# EasyEDA.net
KiCad netlist of a schematic drawn in EasyEDA Pro
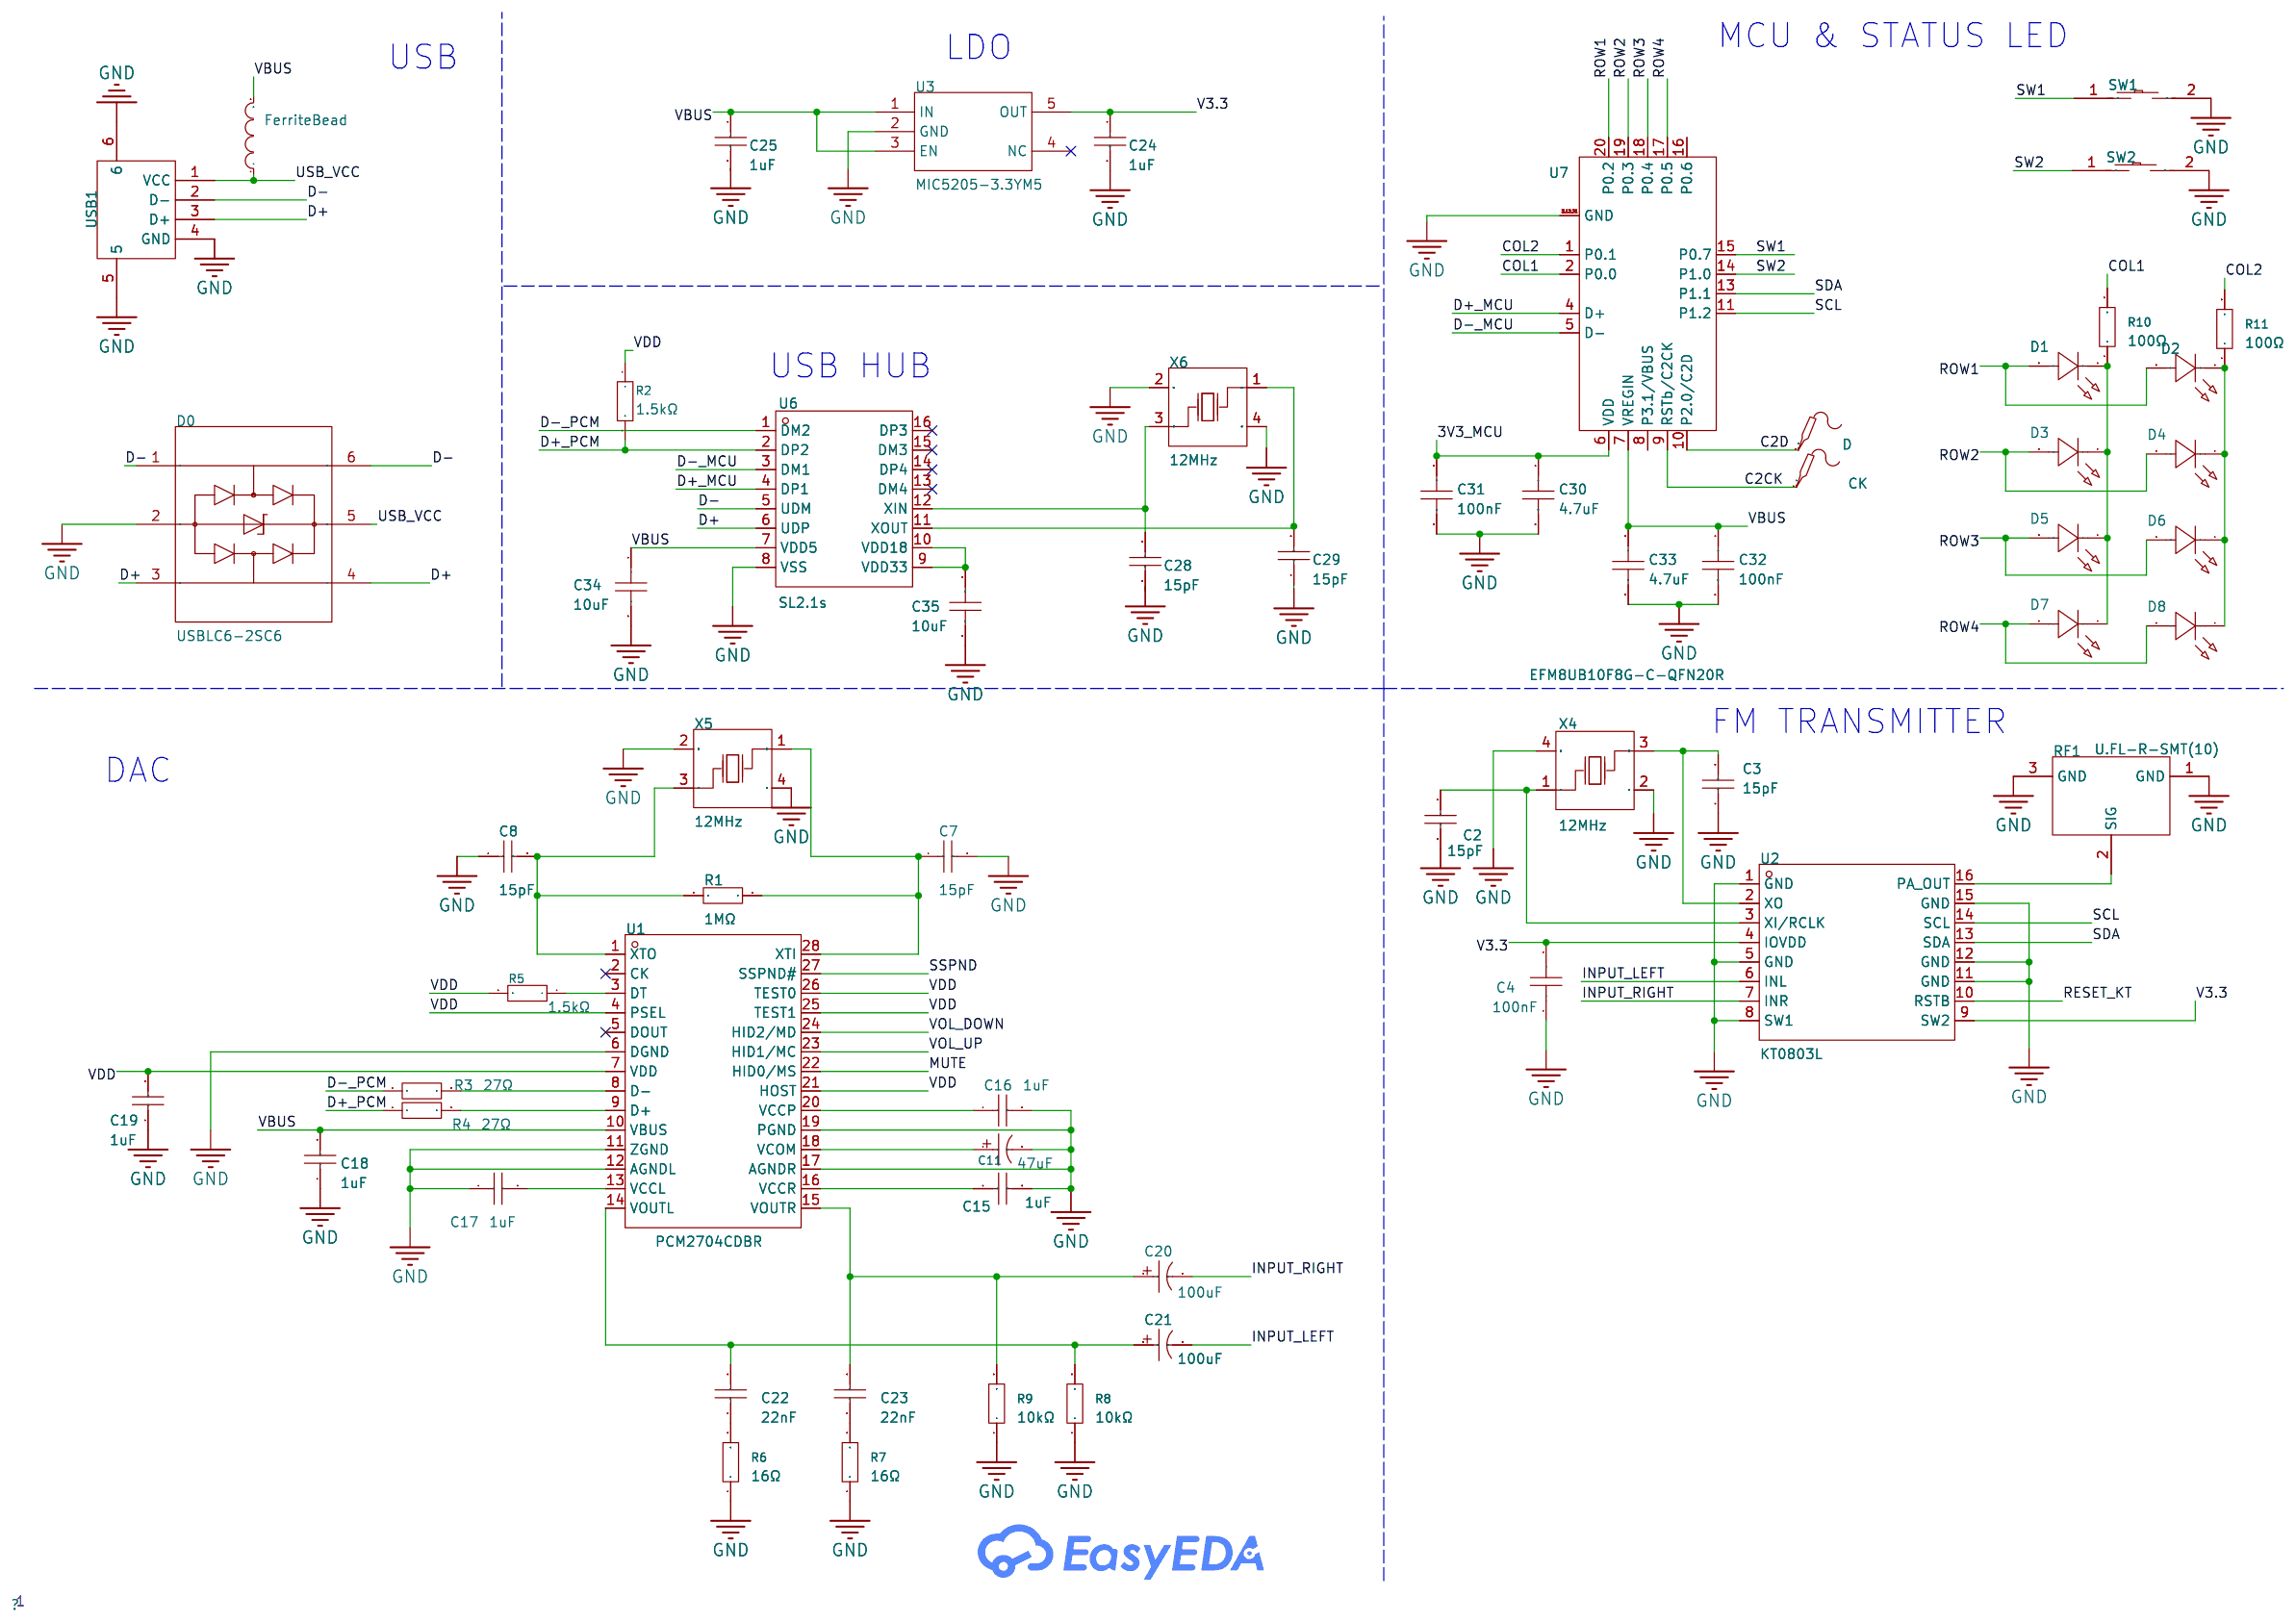
[diagram p0: schematic sheet]

(export (version "E")
  (design (tool "Eeschema 10.0.6"))
  (components
    (comp (ref "C2")
      (value "15pF")
      (footprint "easyedapro:C0402")
      (fields (field (name "Manufacturer Part") "0402CG150J500NT") (field (name "Manufacturer") "FH(风华)"))
      (libsource (lib "easyedapro") (part "0402CG150J500NT"))
    )
    (comp (ref "C3")
      (value "15pF")
      (footprint "easyedapro:C0402")
      (fields (field (name "Manufacturer Part") "0402CG150J500NT") (field (name "Manufacturer") "FH(风华)"))
      (libsource (lib "easyedapro") (part "0402CG150J500NT"))
    )
    (comp (ref "C4")
      (value "100nF")
      (footprint "easyedapro:C0402")
      (fields
        (field (name "Manufacturer Part") "CL05B104KO5NNNC")
        (field (name "Manufacturer") "SAMSUNG(三星)")
      )
      (libsource (lib "easyedapro") (part "CL05B104KO5NNNC"))
    )
    (comp (ref "C7")
      (value "15pF")
      (footprint "easyedapro:C0402")
      (fields (field (name "Manufacturer Part") "0402CG150J500NT") (field (name "Manufacturer") "FH(风华)"))
      (libsource (lib "easyedapro") (part "0402CG150J500NT"))
    )
    (comp (ref "C8")
      (value "15pF")
      (footprint "easyedapro:C0402")
      (fields
        (field (name "Manufacturer Part") "GJM1555C1H150FB01D")
        (field (name "Manufacturer") "muRata(村田)")
      )
      (libsource (lib "easyedapro") (part "0402CG150J500NT"))
    )
    (comp (ref "C11")
      (value "47uF")
      (footprint "easyedapro:CAP-SMD_BD5.0-L5.3-W5.3-FD")
      (fields (field (name "Manufacturer Part") "RVT1C470M0505") (field (name "Manufacturer") "HONOR(荣誉)"))
      (libsource (lib "easyedapro") (part "RVT1C470M0505"))
    )
    (comp (ref "C15")
      (value "1uF")
      (footprint "easyedapro:C0603")
      (fields
        (field (name "Manufacturer Part") "CL05A105KP5NNNC")
        (field (name "Manufacturer") "SAMSUNG(三星)")
      )
      (libsource (lib "easyedapro") (part "CL10A105KO8NNNC"))
    )
    (comp (ref "C16")
      (value "1uF")
      (footprint "easyedapro:C0603")
      (fields
        (field (name "Manufacturer Part") "CL05A105KP5NNNC")
        (field (name "Manufacturer") "SAMSUNG(三星)")
      )
      (libsource (lib "easyedapro") (part "CL10A105KO8NNNC"))
    )
    (comp (ref "C17")
      (value "1uF")
      (footprint "easyedapro:C0603")
      (fields
        (field (name "Manufacturer Part") "CL05A105KP5NNNC")
        (field (name "Manufacturer") "SAMSUNG(三星)")
      )
      (libsource (lib "easyedapro") (part "CL10A105KO8NNNC"))
    )
    (comp (ref "C18")
      (value "1uF")
      (footprint "easyedapro:C0603")
      (fields
        (field (name "Manufacturer Part") "CL05A105KP5NNNC")
        (field (name "Manufacturer") "SAMSUNG(三星)")
      )
      (libsource (lib "easyedapro") (part "CL10A105KO8NNNC"))
    )
    (comp (ref "C19")
      (value "1uF")
      (footprint "easyedapro:C0603")
      (fields
        (field (name "Manufacturer Part") "CL05A105KP5NNNC")
        (field (name "Manufacturer") "SAMSUNG(三星)")
      )
      (libsource (lib "easyedapro") (part "CL10A105KO8NNNC"))
    )
    (comp (ref "C20")
      (value "100uF")
      (footprint "easyedapro:CAP-SMD_BD6.3-L6.6-W6.6-LS7.2-R-RD")
      (fields
        (field (name "Manufacturer Part") "FVH010ADA101M0554")
        (field (name "Manufacturer") "FOSAN(富捷/富信)")
      )
      (libsource (lib "easyedapro") (part "RVT1E101M0607"))
    )
    (comp (ref "C21")
      (value "100uF")
      (footprint "easyedapro:CAP-SMD_BD6.3-L6.6-W6.6-LS7.2-R-RD")
      (fields
        (field (name "Manufacturer Part") "FVH010ADA101M0554")
        (field (name "Manufacturer") "FOSAN(富捷/富信)")
      )
      (libsource (lib "easyedapro") (part "RVT1E101M0607"))
    )
    (comp (ref "C22")
      (value "22nF")
      (footprint "easyedapro:C0402")
      (description "Capacitance:22nF Tolerance:±10% Tolerance:±10% Voltage Rating:50V Temperature Coefficient:X7R")
      (fields (field (name "Manufacturer Part") "0402B223K500NT") (field (name "Manufacturer") "FH(风华)"))
      (libsource (lib "easyedapro") (part "0402B223K500NT"))
    )
    (comp (ref "C23")
      (value "22nF")
      (footprint "easyedapro:C0402")
      (description "Capacitance:22nF Tolerance:±10% Tolerance:±10% Voltage Rating:50V Temperature Coefficient:X7R")
      (fields (field (name "Manufacturer Part") "0402B223K500NT") (field (name "Manufacturer") "FH(风华)"))
      (libsource (lib "easyedapro") (part "0402B223K500NT"))
    )
    (comp (ref "C24")
      (value "1uF")
      (footprint "easyedapro:C0603")
      (fields
        (field (name "Manufacturer Part") "CL05A105KP5NNNC")
        (field (name "Manufacturer") "SAMSUNG(三星)")
      )
      (libsource (lib "easyedapro") (part "CL10A105KO8NNNC"))
    )
    (comp (ref "C25")
      (value "1uF")
      (footprint "easyedapro:C0603")
      (fields
        (field (name "Manufacturer Part") "CL05A105KP5NNNC")
        (field (name "Manufacturer") "SAMSUNG(三星)")
      )
      (libsource (lib "easyedapro") (part "CL10A105KO8NNNC"))
    )
    (comp (ref "C28")
      (value "15pF")
      (footprint "easyedapro:C0402")
      (fields (field (name "Manufacturer Part") "0402CG150J500NT") (field (name "Manufacturer") "FH(风华)"))
      (libsource (lib "easyedapro") (part "0402CG150J500NT"))
    )
    (comp (ref "C29")
      (value "15pF")
      (footprint "easyedapro:C0402")
      (fields (field (name "Manufacturer Part") "0402CG150J500NT") (field (name "Manufacturer") "FH(风华)"))
      (libsource (lib "easyedapro") (part "0402CG150J500NT"))
    )
    (comp (ref "C30")
      (value "4.7uF")
      (footprint "easyedapro:C0402")
      (fields
        (field (name "Manufacturer Part") "CL05A475KP5NRNC")
        (field (name "Manufacturer") "SAMSUNG(三星)")
      )
      (libsource (lib "easyedapro") (part "CAP"))
    )
    (comp (ref "C31")
      (value "100nF")
      (footprint "easyedapro:C0402")
      (fields
        (field (name "Manufacturer Part") "CL05A104KA5NNNC")
        (field (name "Manufacturer") "SAMSUNG(三星)")
      )
      (libsource (lib "easyedapro") (part "CAP"))
    )
    (comp (ref "C32")
      (value "100nF")
      (footprint "easyedapro:C0402")
      (fields
        (field (name "Manufacturer Part") "CL05A104KA5NNNC")
        (field (name "Manufacturer") "SAMSUNG(三星)")
      )
      (libsource (lib "easyedapro") (part "CAP"))
    )
    (comp (ref "C33")
      (value "4.7uF")
      (footprint "easyedapro:C0402")
      (fields
        (field (name "Manufacturer Part") "CL05A475KP5NRNC")
        (field (name "Manufacturer") "SAMSUNG(三星)")
      )
      (libsource (lib "easyedapro") (part "CAP"))
    )
    (comp (ref "C34")
      (value "10uF")
      (footprint "easyedapro:C0402")
      (libsource (lib "easyedapro") (part "CAP"))
    )
    (comp (ref "C35")
      (value "10uF")
      (footprint "easyedapro:C0402")
      (libsource (lib "easyedapro") (part "CAP"))
    )
    (comp (ref "CK")
      (value "~")
      (footprint "easyedapro:Test-Point-0.5mm")
      (description "Test Point 测试点")
      (libsource (lib "easyedapro") (part "Test-Point"))
    )
    (comp (ref "D")
      (value "~")
      (footprint "easyedapro:Test-Point-0.5mm")
      (description "Test Point 测试点")
      (libsource (lib "easyedapro") (part "Test-Point"))
    )
    (comp (ref "D0")
      (value "USBLC6-2SC6")
      (footprint "easyedapro:SOT-23-6_L2.9-W1.6-P0.95-LS2.8-BL")
      (libsource (lib "easyedapro") (part "USBLC6-2SC6_C323793"))
    )
    (comp (ref "D1")
      (value "XL-1005UGC")
      (footprint "easyedapro:LED0402-RD_GREEN")
      (fields (field (name "Manufacturer") "XINGLIGHT(成兴光)"))
      (libsource (lib "easyedapro") (part "XL-1005UGC"))
    )
    (comp (ref "D2")
      (value "XL-1005UGC")
      (footprint "easyedapro:LED0402-RD_GREEN")
      (fields (field (name "Manufacturer") "XINGLIGHT(成兴光)"))
      (libsource (lib "easyedapro") (part "XL-1005UGC"))
    )
    (comp (ref "D3")
      (value "XL-1005UGC")
      (footprint "easyedapro:LED0402-RD_GREEN")
      (fields (field (name "Manufacturer") "XINGLIGHT(成兴光)"))
      (libsource (lib "easyedapro") (part "XL-1005UGC"))
    )
    (comp (ref "D4")
      (value "XL-1005UGC")
      (footprint "easyedapro:LED0402-RD_GREEN")
      (fields (field (name "Manufacturer") "XINGLIGHT(成兴光)"))
      (libsource (lib "easyedapro") (part "XL-1005UGC"))
    )
    (comp (ref "D5")
      (value "XL-1005UGC")
      (footprint "easyedapro:LED0402-RD_GREEN")
      (fields (field (name "Manufacturer") "XINGLIGHT(成兴光)"))
      (libsource (lib "easyedapro") (part "XL-1005UGC"))
    )
    (comp (ref "D6")
      (value "XL-1005UGC")
      (footprint "easyedapro:LED0402-RD_GREEN")
      (fields (field (name "Manufacturer") "XINGLIGHT(成兴光)"))
      (libsource (lib "easyedapro") (part "XL-1005UGC"))
    )
    (comp (ref "D7")
      (value "XL-1005UGC")
      (footprint "easyedapro:LED0402-RD_GREEN")
      (fields (field (name "Manufacturer") "XINGLIGHT(成兴光)"))
      (libsource (lib "easyedapro") (part "XL-1005UGC"))
    )
    (comp (ref "D8")
      (value "XL-1005UGC")
      (footprint "easyedapro:LED0402-RD_GREEN")
      (fields (field (name "Manufacturer") "XINGLIGHT(成兴光)"))
      (libsource (lib "easyedapro") (part "XL-1005UGC"))
    )
    (comp (ref "FerriteBead")
      (value "MPZ2012S601AT000")
      (footprint "easyedapro:L0603")
      (fields (field (name "Manufacturer") "TDK"))
      (libsource (lib "easyedapro") (part "MPZ1608S101ATAH0"))
    )
    (comp (ref "R1")
      (value "1MΩ")
      (footprint "easyedapro:R0402")
      (fields
        (field (name "Manufacturer Part") "0402WGF1004TCE")
        (field (name "Manufacturer") "UNI-ROYAL(厚声)")
      )
      (libsource (lib "easyedapro") (part "1M"))
    )
    (comp (ref "R2")
      (value "1.5kΩ")
      (footprint "easyedapro:R0402")
      (fields
        (field (name "Manufacturer Part") "0402WGF1501TCE")
        (field (name "Manufacturer") "UNI-ROYAL(厚声)")
      )
      (libsource (lib "easyedapro") (part "0402WGF1501TCE"))
    )
    (comp (ref "R3")
      (value "27Ω")
      (footprint "easyedapro:R0402")
      (fields
        (field (name "Manufacturer Part") "0402WGF270JTCE")
        (field (name "Manufacturer") "UNI-ROYAL(厚声)")
      )
      (libsource (lib "easyedapro") (part "0402WGF270JTCE"))
    )
    (comp (ref "R4")
      (value "27Ω")
      (footprint "easyedapro:R0402")
      (fields
        (field (name "Manufacturer Part") "0402WGF270JTCE")
        (field (name "Manufacturer") "UNI-ROYAL(厚声)")
      )
      (libsource (lib "easyedapro") (part "0402WGF270JTCE"))
    )
    (comp (ref "R5")
      (value "1.5kΩ")
      (footprint "easyedapro:R0402")
      (fields
        (field (name "Manufacturer Part") "0402WGF1501TCE")
        (field (name "Manufacturer") "UNI-ROYAL(厚声)")
      )
      (libsource (lib "easyedapro") (part "0402WGF1501TCE"))
    )
    (comp (ref "R6")
      (value "16Ω")
      (footprint "easyedapro:R0603")
      (fields (field (name "Manufacturer Part") "FRC0402F16R0TS") (field (name "Manufacturer") "FOJAN(富捷)"))
      (libsource (lib "easyedapro") (part "0603WAF160JT5E"))
    )
    (comp (ref "R7")
      (value "16Ω")
      (footprint "easyedapro:R0603")
      (fields (field (name "Manufacturer Part") "FRC0402F16R0TS") (field (name "Manufacturer") "FOJAN(富捷)"))
      (libsource (lib "easyedapro") (part "0603WAF160JT5E"))
    )
    (comp (ref "R8")
      (value "10kΩ")
      (footprint "easyedapro:R0402")
      (fields
        (field (name "Manufacturer Part") "0402WGJ0103TCE")
        (field (name "Manufacturer") "UNI-ROYAL(厚声)")
      )
      (libsource (lib "easyedapro") (part "0402WGJ0103TCE"))
    )
    (comp (ref "R9")
      (value "10kΩ")
      (footprint "easyedapro:R0402")
      (fields
        (field (name "Manufacturer Part") "0402WGJ0103TCE")
        (field (name "Manufacturer") "UNI-ROYAL(厚声)")
      )
      (libsource (lib "easyedapro") (part "0402WGJ0103TCE"))
    )
    (comp (ref "R10")
      (value "100Ω")
      (footprint "easyedapro:R0402")
      (fields (field (name "Manufacturer Part") "FRC0402F1000TS") (field (name "Manufacturer") "FOJAN(富捷)"))
      (libsource (lib "easyedapro") (part "0402WGJ0103TCE"))
    )
    (comp (ref "R11")
      (value "100Ω")
      (footprint "easyedapro:R0402")
      (fields (field (name "Manufacturer Part") "FRC0402F1000TS") (field (name "Manufacturer") "FOJAN(富捷)"))
      (libsource (lib "easyedapro") (part "0402WGJ0103TCE"))
    )
    (comp (ref "RF1")
      (value "U.FL-R-SMT(10)")
      (footprint "easyedapro:ANT-SMD_UFL-R-SMT01")
      (fields (field (name "Manufacturer") "HRS(广濑)"))
      (libsource (lib "easyedapro") (part "U.FL-R-SMT(10)"))
    )
    (comp (ref "SW1")
      (value "B3U-1000P")
      (footprint "easyedapro:KEY-SMD_B3U-1000PM")
      (fields (field (name "Manufacturer") "OMRON(欧姆龙)"))
      (libsource (lib "easyedapro") (part "B3U-1000P"))
    )
    (comp (ref "SW2")
      (value "B3U-1000P")
      (footprint "easyedapro:KEY-SMD_B3U-1000PM")
      (fields (field (name "Manufacturer") "OMRON(欧姆龙)"))
      (libsource (lib "easyedapro") (part "B3U-1000P"))
    )
    (comp (ref "U1")
      (value "PCM2704CDBR")
      (footprint "easyedapro:SSOP-28_L10.2-W5.3-P0.65-LS7.8-BL")
      (fields (field (name "Manufacturer") "TI(德州仪器)"))
      (libsource (lib "easyedapro") (part "PCM2704CDBR"))
    )
    (comp (ref "U2")
      (value "KT0803L")
      (footprint "easyedapro:SOP-16_L9.9-W3.9-P1.27-LS6.0-BL")
      (libsource (lib "easyedapro") (part "KT0803L"))
    )
    (comp (ref "U3")
      (value "MIC5205-3.3YM5")
      (footprint "easyedapro:SOT-23-5_L3.0-W1.7-P0.95-LS2.8-BR")
      (fields (field (name "Manufacturer") "TECH PUBLIC(台舟)"))
      (libsource (lib "easyedapro") (part "TLV73333PDBVR"))
    )
    (comp (ref "U6")
      (value "SL2.1s")
      (footprint "easyedapro:SSOP-16_L4.6-W2.6-P0.53-LS4.0-BL")
      (fields (field (name "Manufacturer") "CoreChips(和芯润德)"))
      (libsource (lib "easyedapro") (part "SL2.1S"))
    )
    (comp (ref "U7")
      (value "EFM8UB10F8G-C-QFN20R")
      (footprint "easyedapro:QFN-20_L3.0-W3.0-P0.50-TL-EP1.7_SILICON_C8051F85X")
      (fields (field (name "Manufacturer") "SKYWORKS/SILICON LABS(芯科)"))
      (libsource (lib "easyedapro") (part "EFM8UB10F8G-C-QFN20R"))
    )
    (comp (ref "USB1")
      (value "U-G-O4DD-W-1")
      (footprint "easyedapro:USB-A-TH_U-G-04WD-W-01")
      (fields (field (name "Manufacturer") "韩国韩荣"))
      (libsource (lib "easyedapro") (part "U-G-04DD-W-01"))
    )
    (comp (ref "X4")
      (value "12MHz")
      (footprint "easyedapro:CRYSTAL-SMD_4P-L3.2-W2.5-BL")
      (fields
        (field (name "Manufacturer Part") "SX2B12.000F1010F30")
        (field (name "Manufacturer") "SCTF(星通时频)")
      )
      (libsource (lib "easyedapro") (part "X322512MSB4SI"))
    )
    (comp (ref "X5")
      (value "12MHz")
      (footprint "easyedapro:CRYSTAL-SMD_4P-L3.2-W2.5-BL")
      (fields
        (field (name "Manufacturer Part") "SX2B12.000F1010F30")
        (field (name "Manufacturer") "SCTF(星通时频)")
      )
      (libsource (lib "easyedapro") (part "X322512MSB4SI"))
    )
    (comp (ref "X6")
      (value "12MHz")
      (footprint "easyedapro:CRYSTAL-SMD_4P-L3.2-W2.5-BL")
      (fields
        (field (name "Manufacturer Part") "SX2B12.000F1010F30")
        (field (name "Manufacturer") "SCTF(星通时频)")
      )
      (libsource (lib "easyedapro") (part "X322512MSB4SI"))
    )
  )
  (nets
    (net (code "1") (name "/3V3_MCU") (class "Default")
      (node (ref "C30") (pin "1") (pinfunction "1_1") (pintype "input"))
      (node (ref "C31") (pin "1") (pinfunction "1_1") (pintype "input"))
      (node (ref "U7") (pin "6") (pinfunction "VDD_6") (pintype "unspecified"))
    )
    (net (code "2") (name "/C2CK") (class "Default")
      (node (ref "CK") (pin "1") (pinfunction "1_1") (pintype "unspecified"))
      (node (ref "U7") (pin "9") (pinfunction "RSTb/C2CK_9") (pintype "unspecified"))
    )
    (net (code "3") (name "/C2D") (class "Default")
      (node (ref "D") (pin "1") (pinfunction "1_1") (pintype "unspecified"))
      (node (ref "U7") (pin "10") (pinfunction "P2.0/C2D_10") (pintype "unspecified"))
    )
    (net (code "4") (name "/COL1") (class "Default")
      (node (ref "R10") (pin "2") (pinfunction "2_2") (pintype "input"))
      (node (ref "U7") (pin "2") (pinfunction "P0.0_2") (pintype "unspecified"))
    )
    (net (code "5") (name "/COL2") (class "Default")
      (node (ref "R11") (pin "2") (pinfunction "2_2") (pintype "input"))
      (node (ref "U7") (pin "1") (pinfunction "P0.1_1") (pintype "unspecified"))
    )
    (net (code "6") (name "/D+") (class "Default")
      (node (ref "D0") (pin "3") (pinfunction "3_3") (pintype "input"))
      (node (ref "D0") (pin "4") (pinfunction "4_4") (pintype "input"))
      (node (ref "U6") (pin "6") (pinfunction "UDP_6") (pintype "unspecified"))
      (node (ref "USB1") (pin "3") (pinfunction "D+_3") (pintype "unspecified"))
    )
    (net (code "7") (name "/D+_MCU") (class "Default")
      (node (ref "U6") (pin "4") (pinfunction "DP1_4") (pintype "unspecified"))
      (node (ref "U7") (pin "4") (pinfunction "D+_4") (pintype "unspecified"))
    )
    (net (code "8") (name "/D+_PCM") (class "Default")
      (node (ref "R2") (pin "2") (pinfunction "2_2") (pintype "input"))
      (node (ref "R4") (pin "1") (pinfunction "1_1") (pintype "input"))
      (node (ref "U6") (pin "2") (pinfunction "DP2_2") (pintype "unspecified"))
    )
    (net (code "9") (name "/D-") (class "Default")
      (node (ref "D0") (pin "1") (pinfunction "1_1") (pintype "input"))
      (node (ref "D0") (pin "6") (pinfunction "6_6") (pintype "input"))
      (node (ref "U6") (pin "5") (pinfunction "UDM_5") (pintype "unspecified"))
      (node (ref "USB1") (pin "2") (pinfunction "D-_2") (pintype "unspecified"))
    )
    (net (code "10") (name "/D-_MCU") (class "Default")
      (node (ref "U6") (pin "3") (pinfunction "DM1_3") (pintype "unspecified"))
      (node (ref "U7") (pin "5") (pinfunction "D-_5") (pintype "unspecified"))
    )
    (net (code "11") (name "/D-_PCM") (class "Default")
      (node (ref "R3") (pin "1") (pinfunction "1_1") (pintype "input"))
      (node (ref "U6") (pin "1") (pinfunction "DM2_1") (pintype "unspecified"))
    )
    (net (code "12") (name "/INPUT_LEFT") (class "Default")
      (node (ref "C21") (pin "2") (pinfunction "2_2") (pintype "input"))
      (node (ref "U2") (pin "6") (pinfunction "INL_6") (pintype "unspecified"))
    )
    (net (code "13") (name "/INPUT_RIGHT") (class "Default")
      (node (ref "C20") (pin "2") (pinfunction "2_2") (pintype "input"))
      (node (ref "U2") (pin "7") (pinfunction "INR_7") (pintype "unspecified"))
    )
    (net (code "14") (name "/MUTE") (class "Default")
      (node (ref "U1") (pin "22") (pinfunction "HID0/MS_22") (pintype "unspecified"))
    )
    (net (code "15") (name "/RESET_KT") (class "Default")
      (node (ref "U2") (pin "10") (pinfunction "RSTB_10") (pintype "unspecified"))
    )
    (net (code "16") (name "/ROW1") (class "Default")
      (node (ref "D1") (pin "2") (pinfunction "A_2") (pintype "unspecified"))
      (node (ref "D2") (pin "2") (pinfunction "A_2") (pintype "unspecified"))
      (node (ref "U7") (pin "20") (pinfunction "P0.2_20") (pintype "unspecified"))
    )
    (net (code "17") (name "/ROW2") (class "Default")
      (node (ref "D3") (pin "2") (pinfunction "A_2") (pintype "unspecified"))
      (node (ref "D4") (pin "2") (pinfunction "A_2") (pintype "unspecified"))
      (node (ref "U7") (pin "19") (pinfunction "P0.3_19") (pintype "unspecified"))
    )
    (net (code "18") (name "/ROW3") (class "Default")
      (node (ref "D5") (pin "2") (pinfunction "A_2") (pintype "unspecified"))
      (node (ref "D6") (pin "2") (pinfunction "A_2") (pintype "unspecified"))
      (node (ref "U7") (pin "18") (pinfunction "P0.4_18") (pintype "unspecified"))
    )
    (net (code "19") (name "/ROW4") (class "Default")
      (node (ref "D7") (pin "2") (pinfunction "A_2") (pintype "unspecified"))
      (node (ref "D8") (pin "2") (pinfunction "A_2") (pintype "unspecified"))
      (node (ref "U7") (pin "17") (pinfunction "P0.5_17") (pintype "unspecified"))
    )
    (net (code "20") (name "/SCL") (class "Default")
      (node (ref "U2") (pin "14") (pinfunction "SCL_14") (pintype "unspecified"))
      (node (ref "U7") (pin "11") (pinfunction "P1.2_11") (pintype "unspecified"))
    )
    (net (code "21") (name "/SDA") (class "Default")
      (node (ref "U2") (pin "13") (pinfunction "SDA_13") (pintype "unspecified"))
      (node (ref "U7") (pin "13") (pinfunction "P1.1_13") (pintype "unspecified"))
    )
    (net (code "22") (name "/SSPND") (class "Default")
      (node (ref "U1") (pin "27") (pinfunction "SSPND#_27") (pintype "unspecified"))
    )
    (net (code "23") (name "/SW1") (class "Default")
      (node (ref "SW1") (pin "1") (pinfunction "1_1") (pintype "unspecified"))
      (node (ref "U7") (pin "15") (pinfunction "P0.7_15") (pintype "unspecified"))
    )
    (net (code "24") (name "/SW2") (class "Default")
      (node (ref "SW2") (pin "1") (pinfunction "1_1") (pintype "unspecified"))
      (node (ref "U7") (pin "14") (pinfunction "P1.0_14") (pintype "unspecified"))
    )
    (net (code "25") (name "/USB_VCC") (class "Default")
      (node (ref "D0") (pin "5") (pinfunction "5_5") (pintype "input"))
      (node (ref "FerriteBead") (pin "1") (pinfunction "1_1") (pintype "unspecified"))
      (node (ref "USB1") (pin "1") (pinfunction "VCC_1") (pintype "unspecified"))
    )
    (net (code "26") (name "/V3.3") (class "Default")
      (node (ref "C24") (pin "1") (pinfunction "1_1") (pintype "input"))
      (node (ref "C4") (pin "2") (pinfunction "2_2") (pintype "unspecified"))
      (node (ref "U2") (pin "4") (pinfunction "IOVDD_4") (pintype "unspecified"))
      (node (ref "U2") (pin "9") (pinfunction "SW2_9") (pintype "unspecified"))
      (node (ref "U3") (pin "5") (pinfunction "OUT_5") (pintype "unspecified"))
    )
    (net (code "27") (name "/VBUS") (class "Default")
      (node (ref "C18") (pin "2") (pinfunction "2_2") (pintype "input"))
      (node (ref "C25") (pin "1") (pinfunction "1_1") (pintype "input"))
      (node (ref "C32") (pin "1") (pinfunction "1_1") (pintype "input"))
      (node (ref "C33") (pin "1") (pinfunction "1_1") (pintype "input"))
      (node (ref "C34") (pin "1") (pinfunction "1_1") (pintype "input"))
      (node (ref "FerriteBead") (pin "2") (pinfunction "2_2") (pintype "unspecified"))
      (node (ref "U1") (pin "10") (pinfunction "VBUS_10") (pintype "unspecified"))
      (node (ref "U3") (pin "1") (pinfunction "IN_1") (pintype "unspecified"))
      (node (ref "U3") (pin "3") (pinfunction "EN_3") (pintype "unspecified"))
      (node (ref "U6") (pin "7") (pinfunction "VDD5_7") (pintype "unspecified"))
      (node (ref "U7") (pin "7") (pinfunction "VREGIN_7") (pintype "unspecified"))
    )
    (net (code "28") (name "/VDD") (class "Default")
      (node (ref "C19") (pin "2") (pinfunction "2_2") (pintype "input"))
      (node (ref "R2") (pin "1") (pinfunction "1_1") (pintype "input"))
      (node (ref "R5") (pin "2") (pinfunction "2_2") (pintype "input"))
      (node (ref "U1") (pin "21") (pinfunction "HOST_21") (pintype "unspecified"))
      (node (ref "U1") (pin "25") (pinfunction "TEST1_25") (pintype "unspecified"))
      (node (ref "U1") (pin "26") (pinfunction "TEST0_26") (pintype "unspecified"))
      (node (ref "U1") (pin "4") (pinfunction "PSEL_4") (pintype "unspecified"))
      (node (ref "U1") (pin "7") (pinfunction "VDD_7") (pintype "unspecified"))
    )
    (net (code "29") (name "/VOL_DOWN") (class "Default")
      (node (ref "U1") (pin "24") (pinfunction "HID2/MD_24") (pintype "unspecified"))
    )
    (net (code "30") (name "/VOL_UP") (class "Default")
      (node (ref "U1") (pin "23") (pinfunction "HID1/MC_23") (pintype "unspecified"))
    )
    (net (code "31") (name "GND") (class "Default")
      (node (ref "C11") (pin "2") (pinfunction "2_2") (pintype "input"))
      (node (ref "C15") (pin "2") (pinfunction "2_2") (pintype "input"))
      (node (ref "C16") (pin "2") (pinfunction "2_2") (pintype "input"))
      (node (ref "C17") (pin "1") (pinfunction "1_1") (pintype "input"))
      (node (ref "C18") (pin "1") (pinfunction "1_1") (pintype "input"))
      (node (ref "C19") (pin "1") (pinfunction "1_1") (pintype "input"))
      (node (ref "C2") (pin "1") (pinfunction "1_1") (pintype "input"))
      (node (ref "C24") (pin "2") (pinfunction "2_2") (pintype "input"))
      (node (ref "C25") (pin "2") (pinfunction "2_2") (pintype "input"))
      (node (ref "C28") (pin "1") (pinfunction "1_1") (pintype "input"))
      (node (ref "C29") (pin "1") (pinfunction "1_1") (pintype "input"))
      (node (ref "C3") (pin "1") (pinfunction "1_1") (pintype "input"))
      (node (ref "C30") (pin "2") (pinfunction "2_2") (pintype "input"))
      (node (ref "C31") (pin "2") (pinfunction "2_2") (pintype "input"))
      (node (ref "C32") (pin "2") (pinfunction "2_2") (pintype "input"))
      (node (ref "C33") (pin "2") (pinfunction "2_2") (pintype "input"))
      (node (ref "C34") (pin "2") (pinfunction "2_2") (pintype "input"))
      (node (ref "C35") (pin "2") (pinfunction "2_2") (pintype "input"))
      (node (ref "C4") (pin "1") (pinfunction "1_1") (pintype "unspecified"))
      (node (ref "C7") (pin "2") (pinfunction "2_2") (pintype "input"))
      (node (ref "C8") (pin "1") (pinfunction "1_1") (pintype "input"))
      (node (ref "D0") (pin "2") (pinfunction "2_2") (pintype "input"))
      (node (ref "R6") (pin "1") (pinfunction "1_1") (pintype "input"))
      (node (ref "R7") (pin "1") (pinfunction "1_1") (pintype "input"))
      (node (ref "R8") (pin "1") (pinfunction "1_1") (pintype "input"))
      (node (ref "R9") (pin "1") (pinfunction "1_1") (pintype "input"))
      (node (ref "RF1") (pin "1") (pinfunction "GND_1") (pintype "unspecified"))
      (node (ref "RF1") (pin "3") (pinfunction "GND_3") (pintype "unspecified"))
      (node (ref "SW1") (pin "2") (pinfunction "2_2") (pintype "unspecified"))
      (node (ref "SW2") (pin "2") (pinfunction "2_2") (pintype "unspecified"))
      (node (ref "U1") (pin "11") (pinfunction "ZGND_11") (pintype "unspecified"))
      (node (ref "U1") (pin "12") (pinfunction "AGNDL_12") (pintype "unspecified"))
      (node (ref "U1") (pin "17") (pinfunction "AGNDR_17") (pintype "unspecified"))
      (node (ref "U1") (pin "19") (pinfunction "PGND_19") (pintype "unspecified"))
      (node (ref "U1") (pin "6") (pinfunction "DGND_6") (pintype "unspecified"))
      (node (ref "U2") (pin "1") (pinfunction "GND_1") (pintype "unspecified"))
      (node (ref "U2") (pin "11") (pinfunction "GND_11") (pintype "unspecified"))
      (node (ref "U2") (pin "12") (pinfunction "GND_12") (pintype "unspecified"))
      (node (ref "U2") (pin "15") (pinfunction "GND_15") (pintype "unspecified"))
      (node (ref "U2") (pin "5") (pinfunction "GND_5") (pintype "unspecified"))
      (node (ref "U2") (pin "8") (pinfunction "SW1_8") (pintype "unspecified"))
      (node (ref "U3") (pin "2") (pinfunction "GND_2") (pintype "unspecified"))
      (node (ref "U6") (pin "8") (pinfunction "VSS_8") (pintype "unspecified"))
      (node (ref "U7") (pin "3,12,21") (pinfunction "GND_3,12,21") (pintype "unspecified"))
      (node (ref "USB1") (pin "4") (pinfunction "GND_4") (pintype "unspecified"))
      (node (ref "USB1") (pin "5") (pinfunction "5_5") (pintype "unspecified"))
      (node (ref "USB1") (pin "6") (pinfunction "6_6") (pintype "unspecified"))
      (node (ref "X4") (pin "2") (pinfunction "GND_2") (pintype "unspecified"))
      (node (ref "X4") (pin "4") (pinfunction "GND_4") (pintype "unspecified"))
      (node (ref "X5") (pin "2") (pinfunction "GND_2") (pintype "unspecified"))
      (node (ref "X5") (pin "4") (pinfunction "GND_4") (pintype "unspecified"))
      (node (ref "X6") (pin "2") (pinfunction "GND_2") (pintype "unspecified"))
      (node (ref "X6") (pin "4") (pinfunction "GND_4") (pintype "unspecified"))
    )
    (net (code "32") (name "Net-(C22-Pad1)") (class "Default")
      (node (ref "C22") (pin "1") (pinfunction "1_1") (pintype "input"))
      (node (ref "R6") (pin "2") (pinfunction "2_2") (pintype "input"))
    )
    (net (code "33") (name "Net-(C23-Pad1)") (class "Default")
      (node (ref "C23") (pin "1") (pinfunction "1_1") (pintype "input"))
      (node (ref "R7") (pin "2") (pinfunction "2_2") (pintype "input"))
    )
    (net (code "34") (name "Net-(D1-K)") (class "Default")
      (node (ref "D1") (pin "1") (pinfunction "K_1") (pintype "unspecified"))
      (node (ref "D3") (pin "1") (pinfunction "K_1") (pintype "unspecified"))
      (node (ref "D5") (pin "1") (pinfunction "K_1") (pintype "unspecified"))
      (node (ref "D7") (pin "1") (pinfunction "K_1") (pintype "unspecified"))
      (node (ref "R10") (pin "1") (pinfunction "1_1") (pintype "input"))
    )
    (net (code "35") (name "Net-(D2-K)") (class "Default")
      (node (ref "D2") (pin "1") (pinfunction "K_1") (pintype "unspecified"))
      (node (ref "D4") (pin "1") (pinfunction "K_1") (pintype "unspecified"))
      (node (ref "D6") (pin "1") (pinfunction "K_1") (pintype "unspecified"))
      (node (ref "D8") (pin "1") (pinfunction "K_1") (pintype "unspecified"))
      (node (ref "R11") (pin "1") (pinfunction "1_1") (pintype "input"))
    )
    (net (code "36") (name "Net-(RF1-SIG)") (class "Default")
      (node (ref "RF1") (pin "2") (pinfunction "SIG_2") (pintype "unspecified"))
      (node (ref "U2") (pin "16") (pinfunction "PA_OUT_16") (pintype "unspecified"))
    )
    (net (code "37") (name "Net-(U1-D+)") (class "Default")
      (node (ref "R4") (pin "2") (pinfunction "2_2") (pintype "input"))
      (node (ref "U1") (pin "9") (pinfunction "D+_9") (pintype "unspecified"))
    )
    (net (code "38") (name "Net-(U1-D-)") (class "Default")
      (node (ref "R3") (pin "2") (pinfunction "2_2") (pintype "input"))
      (node (ref "U1") (pin "8") (pinfunction "D-_8") (pintype "unspecified"))
    )
    (net (code "39") (name "Net-(U1-DT)") (class "Default")
      (node (ref "R5") (pin "1") (pinfunction "1_1") (pintype "input"))
      (node (ref "U1") (pin "3") (pinfunction "DT_3") (pintype "unspecified"))
    )
    (net (code "40") (name "Net-(U1-VCCL)") (class "Default")
      (node (ref "C17") (pin "2") (pinfunction "2_2") (pintype "input"))
      (node (ref "U1") (pin "13") (pinfunction "VCCL_13") (pintype "unspecified"))
    )
    (net (code "41") (name "Net-(U1-VCCP)") (class "Default")
      (node (ref "C16") (pin "1") (pinfunction "1_1") (pintype "input"))
      (node (ref "U1") (pin "20") (pinfunction "VCCP_20") (pintype "unspecified"))
    )
    (net (code "42") (name "Net-(U1-VCCR)") (class "Default")
      (node (ref "C15") (pin "1") (pinfunction "1_1") (pintype "input"))
      (node (ref "U1") (pin "16") (pinfunction "VCCR_16") (pintype "unspecified"))
    )
    (net (code "43") (name "Net-(U1-VCOM)") (class "Default")
      (node (ref "C11") (pin "1") (pinfunction "1_1") (pintype "input"))
      (node (ref "U1") (pin "18") (pinfunction "VCOM_18") (pintype "unspecified"))
    )
    (net (code "44") (name "Net-(U1-VOUTL)") (class "Default")
      (node (ref "C21") (pin "1") (pinfunction "1_1") (pintype "input"))
      (node (ref "C22") (pin "2") (pinfunction "2_2") (pintype "input"))
      (node (ref "R8") (pin "2") (pinfunction "2_2") (pintype "input"))
      (node (ref "U1") (pin "14") (pinfunction "VOUTL_14") (pintype "unspecified"))
    )
    (net (code "45") (name "Net-(U1-VOUTR)") (class "Default")
      (node (ref "C20") (pin "1") (pinfunction "1_1") (pintype "input"))
      (node (ref "C23") (pin "2") (pinfunction "2_2") (pintype "input"))
      (node (ref "R9") (pin "2") (pinfunction "2_2") (pintype "input"))
      (node (ref "U1") (pin "15") (pinfunction "VOUTR_15") (pintype "unspecified"))
    )
    (net (code "46") (name "Net-(U1-XTI)") (class "Default")
      (node (ref "C7") (pin "1") (pinfunction "1_1") (pintype "input"))
      (node (ref "R1") (pin "2") (pinfunction "2_2") (pintype "input"))
      (node (ref "U1") (pin "28") (pinfunction "XTI_28") (pintype "unspecified"))
      (node (ref "X5") (pin "1") (pinfunction "OSC1_1") (pintype "unspecified"))
    )
    (net (code "47") (name "Net-(U1-XTO)") (class "Default")
      (node (ref "C8") (pin "2") (pinfunction "2_2") (pintype "input"))
      (node (ref "R1") (pin "1") (pinfunction "1_1") (pintype "input"))
      (node (ref "U1") (pin "1") (pinfunction "XTO_1") (pintype "unspecified"))
      (node (ref "X5") (pin "3") (pinfunction "OSC2_3") (pintype "unspecified"))
    )
    (net (code "48") (name "Net-(U2-XI{slash}RCLK)") (class "Default")
      (node (ref "C2") (pin "2") (pinfunction "2_2") (pintype "input"))
      (node (ref "U2") (pin "3") (pinfunction "XI/RCLK_3") (pintype "unspecified"))
      (node (ref "X4") (pin "1") (pinfunction "OSC1_1") (pintype "unspecified"))
    )
    (net (code "49") (name "Net-(U2-XO)") (class "Default")
      (node (ref "C3") (pin "2") (pinfunction "2_2") (pintype "input"))
      (node (ref "U2") (pin "2") (pinfunction "XO_2") (pintype "unspecified"))
      (node (ref "X4") (pin "3") (pinfunction "OSC2_3") (pintype "unspecified"))
    )
    (net (code "50") (name "Net-(U6-VDD18)") (class "Default")
      (node (ref "C35") (pin "1") (pinfunction "1_1") (pintype "input"))
      (node (ref "U6") (pin "10") (pinfunction "VDD18_10") (pintype "unspecified"))
      (node (ref "U6") (pin "9") (pinfunction "VDD33_9") (pintype "unspecified"))
    )
    (net (code "51") (name "Net-(U6-XIN)") (class "Default")
      (node (ref "C28") (pin "2") (pinfunction "2_2") (pintype "input"))
      (node (ref "U6") (pin "12") (pinfunction "XIN_12") (pintype "unspecified"))
      (node (ref "X6") (pin "3") (pinfunction "OSC2_3") (pintype "unspecified"))
    )
    (net (code "52") (name "Net-(U6-XOUT)") (class "Default")
      (node (ref "C29") (pin "2") (pinfunction "2_2") (pintype "input"))
      (node (ref "U6") (pin "11") (pinfunction "XOUT_11") (pintype "unspecified"))
      (node (ref "X6") (pin "1") (pinfunction "OSC1_1") (pintype "unspecified"))
    )
    (net (code "53") (name "unconnected-(U1-CK-Pad2)") (class "Default")
      (node (ref "U1") (pin "2") (pinfunction "CK_2") (pintype "unspecified+no_connect"))
    )
    (net (code "54") (name "unconnected-(U1-DOUT-Pad5)") (class "Default")
      (node (ref "U1") (pin "5") (pinfunction "DOUT_5") (pintype "unspecified+no_connect"))
    )
    (net (code "55") (name "unconnected-(U3-NC-Pad4)") (class "Default")
      (node (ref "U3") (pin "4") (pinfunction "NC_4") (pintype "unspecified+no_connect"))
    )
    (net (code "56") (name "unconnected-(U6-DM3-Pad15)") (class "Default")
      (node (ref "U6") (pin "15") (pinfunction "DM3_15") (pintype "unspecified+no_connect"))
    )
    (net (code "57") (name "unconnected-(U6-DM4-Pad13)") (class "Default")
      (node (ref "U6") (pin "13") (pinfunction "DM4_13") (pintype "unspecified+no_connect"))
    )
    (net (code "58") (name "unconnected-(U6-DP3-Pad16)") (class "Default")
      (node (ref "U6") (pin "16") (pinfunction "DP3_16") (pintype "unspecified+no_connect"))
    )
    (net (code "59") (name "unconnected-(U6-DP4-Pad14)") (class "Default")
      (node (ref "U6") (pin "14") (pinfunction "DP4_14") (pintype "unspecified+no_connect"))
    )
    (net (code "60") (name "unconnected-(U7-P0.6-Pad16)") (class "Default")
      (node (ref "U7") (pin "16") (pinfunction "P0.6_16") (pintype "unspecified"))
    )
    (net (code "61") (name "unconnected-(U7-P3.1{slash}VBUS-Pad8)") (class "Default")
      (node (ref "U7") (pin "8") (pinfunction "P3.1/VBUS_8") (pintype "unspecified"))
    )
  )
)
